# Laserschwert.net
KiCad netlist of a schematic drawn in EAGLE
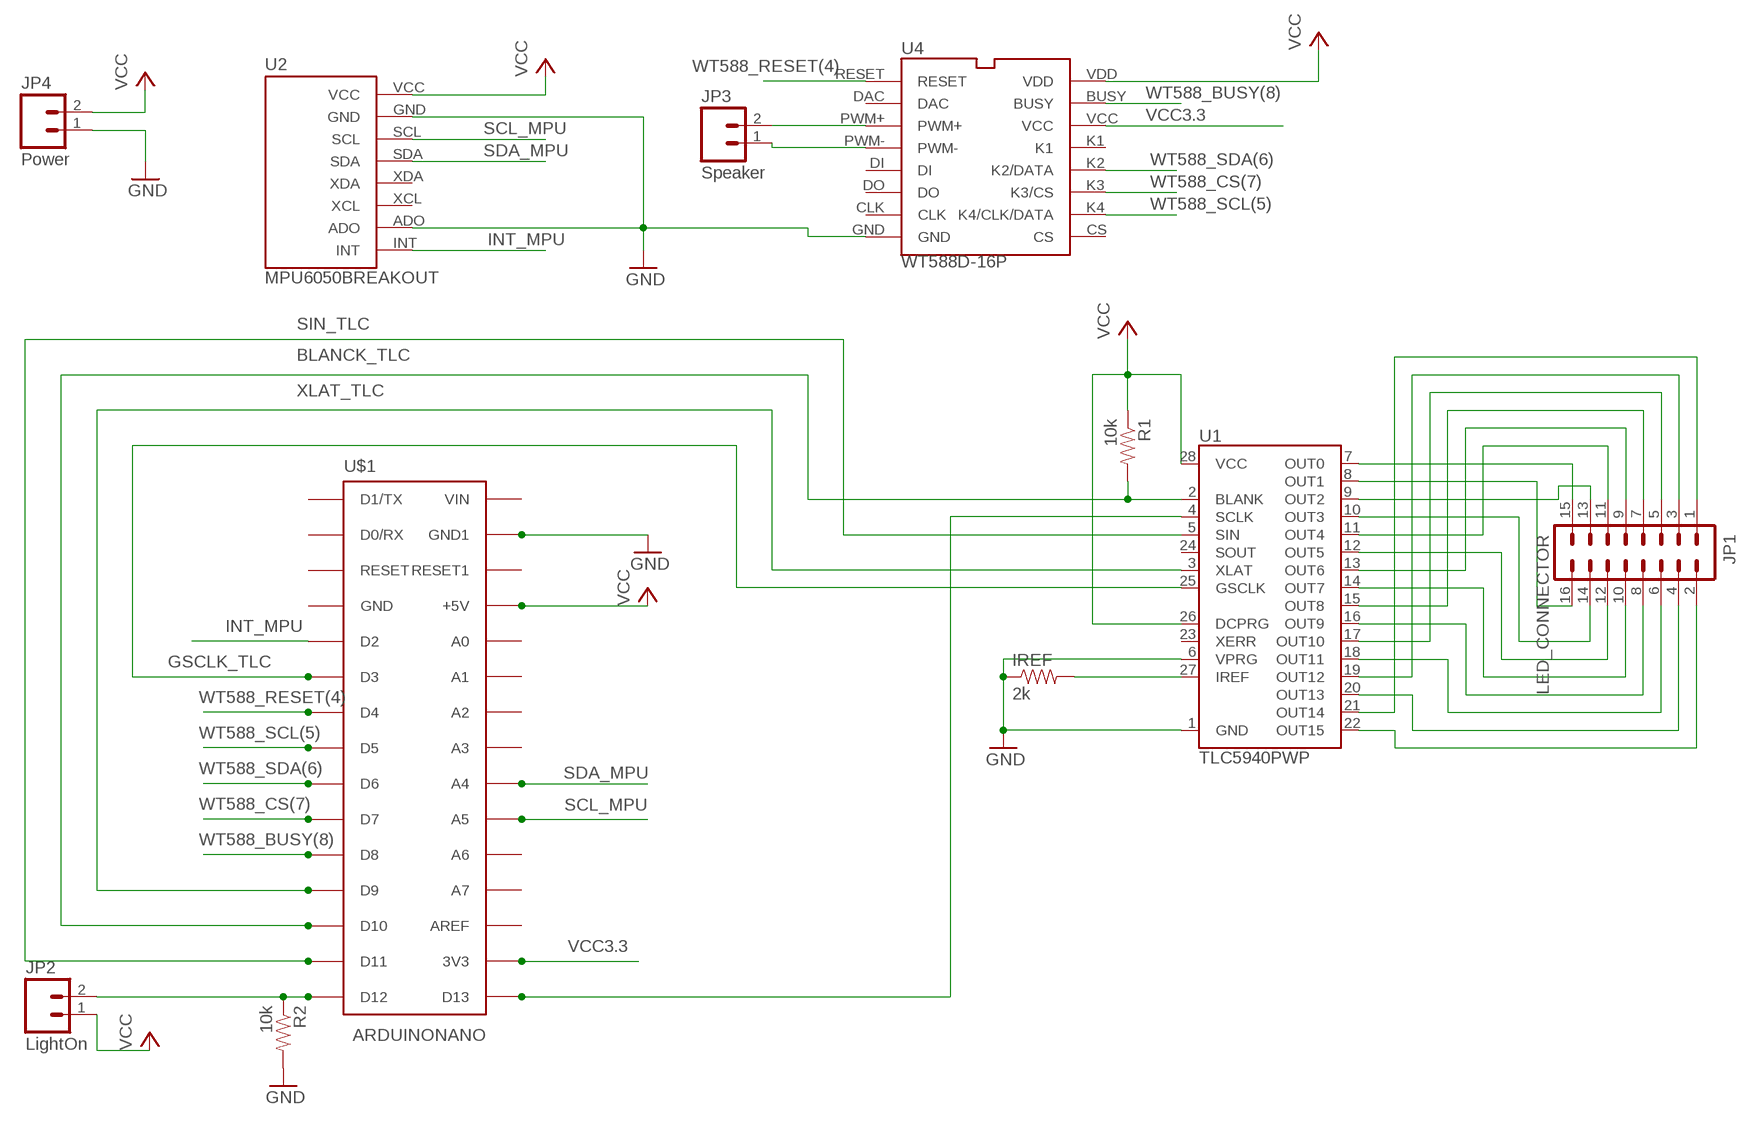
[diagram p0: schematic, sheet 1]

(export (version "E")
  (design (tool "Eeschema 10.0.6"))
  (components
    (comp (ref "IREF")
      (value "2k")
      (footprint "eagle-import:0805")
      (libsource (lib "eagle-import") (part "RESISTOR0805-RES"))
    )
    (comp (ref "JP1")
      (value "LED_CONNECTOR")
      (footprint "eagle-import:2X8")
      (libsource (lib "eagle-import") (part "M08X2"))
    )
    (comp (ref "JP2")
      (value "LightOn")
      (footprint "eagle-import:1X02")
      (libsource (lib "eagle-import") (part "M02PTH"))
    )
    (comp (ref "JP3")
      (value "Speaker")
      (footprint "eagle-import:1X02")
      (libsource (lib "eagle-import") (part "M02PTH"))
    )
    (comp (ref "JP4")
      (value "Power")
      (footprint "eagle-import:1X02")
      (libsource (lib "eagle-import") (part "M02PTH"))
    )
    (comp (ref "R1")
      (value "10k")
      (footprint "eagle-import:0805")
      (libsource (lib "eagle-import") (part "RESISTOR0805-RES"))
    )
    (comp (ref "R2")
      (value "10k")
      (footprint "eagle-import:0805")
      (libsource (lib "eagle-import") (part "RESISTOR0805-RES"))
    )
    (comp (ref "U$1")
      (value "ARDUINONANO")
      (footprint "eagle-import:PDIP-32")
      (libsource (lib "eagle-import") (part "ARDUINONANO"))
    )
    (comp (ref "U1")
      (value "TLC5940PWP")
      (footprint "eagle-import:TSSOP28-GROUNDPAD")
      (libsource (lib "eagle-import") (part "TLC5940PWP"))
    )
    (comp (ref "U2")
      (value "MPU6050BREAKOUT")
      (footprint "eagle-import:PDIP-8")
      (libsource (lib "eagle-import") (part "MPU6050BREAKOUT"))
    )
    (comp (ref "U4")
      (value "WT588D-16P")
      (footprint "eagle-import:PDIP-16")
      (libsource (lib "eagle-import") (part "WT588D-16P"))
    )
  )
  (nets
    (net (code "1") (name "/BLANCK_TLC") (class "Default")
      (node (ref "R1") (pin "2") (pinfunction "2_2") (pintype "passive"))
      (node (ref "U$1") (pin "D10") (pinfunction "D10_D10") (pintype "bidirectional"))
      (node (ref "U1") (pin "2") (pinfunction "BLANK_2") (pintype "bidirectional"))
    )
    (net (code "2") (name "/GSCLK_TLC") (class "Default")
      (node (ref "U$1") (pin "D3") (pinfunction "D3_D3") (pintype "bidirectional"))
      (node (ref "U1") (pin "25") (pinfunction "GSCLK_25") (pintype "bidirectional"))
    )
    (net (code "3") (name "/INT_MPU") (class "Default")
      (node (ref "U$1") (pin "D2") (pinfunction "D2_D2") (pintype "bidirectional"))
      (node (ref "U2") (pin "INT") (pinfunction "INT_INT") (pintype "bidirectional"))
    )
    (net (code "4") (name "/SCL_MPU") (class "Default")
      (node (ref "U$1") (pin "A5") (pinfunction "A5_A5") (pintype "bidirectional"))
      (node (ref "U2") (pin "SCL") (pinfunction "SCL_SCL") (pintype "bidirectional"))
    )
    (net (code "5") (name "/SDA_MPU") (class "Default")
      (node (ref "U$1") (pin "A4") (pinfunction "A4_A4") (pintype "bidirectional"))
      (node (ref "U2") (pin "SDA") (pinfunction "SDA_SDA") (pintype "bidirectional"))
    )
    (net (code "6") (name "/SIN_TLC") (class "Default")
      (node (ref "U$1") (pin "D11") (pinfunction "D11_D11") (pintype "bidirectional"))
      (node (ref "U1") (pin "5") (pinfunction "SIN_5") (pintype "bidirectional"))
    )
    (net (code "7") (name "/VCC3.3") (class "Default")
      (node (ref "U$1") (pin "3V3") (pinfunction "3V3_3V3") (pintype "bidirectional"))
      (node (ref "U4") (pin "VCC") (pinfunction "VCC_VCC") (pintype "power_in"))
    )
    (net (code "8") (name "/WT588_BUSY(8)") (class "Default")
      (node (ref "U$1") (pin "D8") (pinfunction "D8_D8") (pintype "bidirectional"))
      (node (ref "U4") (pin "BUSY") (pinfunction "BUSY_BUSY") (pintype "output"))
    )
    (net (code "9") (name "/WT588_CS(7)") (class "Default")
      (node (ref "U$1") (pin "D7") (pinfunction "D7_D7") (pintype "bidirectional"))
      (node (ref "U4") (pin "K3") (pinfunction "K3/CS_K3") (pintype "bidirectional"))
    )
    (net (code "10") (name "/WT588_RESET(4)") (class "Default")
      (node (ref "U$1") (pin "D4") (pinfunction "D4_D4") (pintype "bidirectional"))
      (node (ref "U4") (pin "RESET") (pinfunction "RESET_RESET") (pintype "bidirectional"))
    )
    (net (code "11") (name "/WT588_SCL(5)") (class "Default")
      (node (ref "U$1") (pin "D5") (pinfunction "D5_D5") (pintype "bidirectional"))
      (node (ref "U4") (pin "K4") (pinfunction "K4/CLK/DATA_K4") (pintype "bidirectional"))
    )
    (net (code "12") (name "/WT588_SDA(6)") (class "Default")
      (node (ref "U$1") (pin "D6") (pinfunction "D6_D6") (pintype "bidirectional"))
      (node (ref "U4") (pin "K2") (pinfunction "K2/DATA_K2") (pintype "bidirectional"))
    )
    (net (code "13") (name "/XLAT_TLC") (class "Default")
      (node (ref "U$1") (pin "D9") (pinfunction "D9_D9") (pintype "bidirectional"))
      (node (ref "U1") (pin "3") (pinfunction "XLAT_3") (pintype "bidirectional"))
    )
    (net (code "14") (name "GND") (class "Default")
      (node (ref "IREF") (pin "1") (pinfunction "1_1") (pintype "passive"))
      (node (ref "JP4") (pin "1") (pinfunction "1_1") (pintype "passive"))
      (node (ref "R2") (pin "2") (pinfunction "2_2") (pintype "passive"))
      (node (ref "U$1") (pin "GND1") (pinfunction "GND1_GND1") (pintype "bidirectional"))
      (node (ref "U1") (pin "1") (pinfunction "GND_1") (pintype "bidirectional"))
      (node (ref "U1") (pin "6") (pinfunction "VPRG_6") (pintype "bidirectional"))
      (node (ref "U2") (pin "ADO") (pinfunction "ADO_ADO") (pintype "bidirectional"))
      (node (ref "U2") (pin "GND") (pinfunction "GND_GND") (pintype "power_in"))
      (node (ref "U4") (pin "GND") (pinfunction "GND_GND") (pintype "power_in"))
    )
    (net (code "15") (name "Net-(JP2-Pad2)") (class "Default")
      (node (ref "JP2") (pin "2") (pinfunction "2_2") (pintype "passive"))
      (node (ref "R2") (pin "1") (pinfunction "1_1") (pintype "passive"))
      (node (ref "U$1") (pin "D12") (pinfunction "D12_D12") (pintype "bidirectional"))
    )
    (net (code "16") (name "Net-(JP3-Pad1)") (class "Default")
      (node (ref "JP3") (pin "1") (pinfunction "1_1") (pintype "passive"))
      (node (ref "U4") (pin "PWM-") (pinfunction "PWM-_PWM-") (pintype "bidirectional"))
    )
    (net (code "17") (name "Net-(JP3-Pad2)") (class "Default")
      (node (ref "JP3") (pin "2") (pinfunction "2_2") (pintype "passive"))
      (node (ref "U4") (pin "PWM+") (pinfunction "PWM+_PWM+") (pintype "bidirectional"))
    )
    (net (code "18") (name "Net-(U1-IREF)") (class "Default")
      (node (ref "IREF") (pin "2") (pinfunction "2_2") (pintype "passive"))
      (node (ref "U1") (pin "27") (pinfunction "IREF_27") (pintype "bidirectional"))
    )
    (net (code "19") (name "Net-(U1-OUT0)") (class "Default")
      (node (ref "JP1") (pin "15") (pinfunction "15_15") (pintype "passive"))
      (node (ref "U1") (pin "7") (pinfunction "OUT0_7") (pintype "bidirectional"))
    )
    (net (code "20") (name "Net-(U1-OUT1)") (class "Default")
      (node (ref "JP1") (pin "16") (pinfunction "16_16") (pintype "passive"))
      (node (ref "U1") (pin "8") (pinfunction "OUT1_8") (pintype "bidirectional"))
    )
    (net (code "21") (name "Net-(U1-OUT2)") (class "Default")
      (node (ref "JP1") (pin "13") (pinfunction "13_13") (pintype "passive"))
      (node (ref "U1") (pin "9") (pinfunction "OUT2_9") (pintype "bidirectional"))
    )
    (net (code "22") (name "Net-(U1-OUT3)") (class "Default")
      (node (ref "JP1") (pin "14") (pinfunction "14_14") (pintype "passive"))
      (node (ref "U1") (pin "10") (pinfunction "OUT3_10") (pintype "bidirectional"))
    )
    (net (code "23") (name "Net-(U1-OUT4)") (class "Default")
      (node (ref "JP1") (pin "11") (pinfunction "11_11") (pintype "passive"))
      (node (ref "U1") (pin "11") (pinfunction "OUT4_11") (pintype "bidirectional"))
    )
    (net (code "24") (name "Net-(U1-OUT5)") (class "Default")
      (node (ref "JP1") (pin "12") (pinfunction "12_12") (pintype "passive"))
      (node (ref "U1") (pin "12") (pinfunction "OUT5_12") (pintype "bidirectional"))
    )
    (net (code "25") (name "Net-(U1-OUT6)") (class "Default")
      (node (ref "JP1") (pin "9") (pinfunction "9_9") (pintype "passive"))
      (node (ref "U1") (pin "13") (pinfunction "OUT6_13") (pintype "bidirectional"))
    )
    (net (code "26") (name "Net-(U1-OUT7)") (class "Default")
      (node (ref "JP1") (pin "10") (pinfunction "10_10") (pintype "passive"))
      (node (ref "U1") (pin "14") (pinfunction "OUT7_14") (pintype "bidirectional"))
    )
    (net (code "27") (name "Net-(U1-OUT8)") (class "Default")
      (node (ref "JP1") (pin "7") (pinfunction "7_7") (pintype "passive"))
      (node (ref "U1") (pin "15") (pinfunction "OUT8_15") (pintype "bidirectional"))
    )
    (net (code "28") (name "Net-(U1-OUT9)") (class "Default")
      (node (ref "JP1") (pin "8") (pinfunction "8_8") (pintype "passive"))
      (node (ref "U1") (pin "16") (pinfunction "OUT9_16") (pintype "bidirectional"))
    )
    (net (code "29") (name "Net-(U1-OUT10)") (class "Default")
      (node (ref "JP1") (pin "5") (pinfunction "5_5") (pintype "passive"))
      (node (ref "U1") (pin "17") (pinfunction "OUT10_17") (pintype "bidirectional"))
    )
    (net (code "30") (name "Net-(U1-OUT11)") (class "Default")
      (node (ref "JP1") (pin "6") (pinfunction "6_6") (pintype "passive"))
      (node (ref "U1") (pin "18") (pinfunction "OUT11_18") (pintype "bidirectional"))
    )
    (net (code "31") (name "Net-(U1-OUT12)") (class "Default")
      (node (ref "JP1") (pin "3") (pinfunction "3_3") (pintype "passive"))
      (node (ref "U1") (pin "19") (pinfunction "OUT12_19") (pintype "bidirectional"))
    )
    (net (code "32") (name "Net-(U1-OUT13)") (class "Default")
      (node (ref "JP1") (pin "4") (pinfunction "4_4") (pintype "passive"))
      (node (ref "U1") (pin "20") (pinfunction "OUT13_20") (pintype "bidirectional"))
    )
    (net (code "33") (name "Net-(U1-OUT14)") (class "Default")
      (node (ref "JP1") (pin "1") (pinfunction "1_1") (pintype "passive"))
      (node (ref "U1") (pin "21") (pinfunction "OUT14_21") (pintype "bidirectional"))
    )
    (net (code "34") (name "Net-(U1-OUT15)") (class "Default")
      (node (ref "JP1") (pin "2") (pinfunction "2_2") (pintype "passive"))
      (node (ref "U1") (pin "22") (pinfunction "OUT15_22") (pintype "bidirectional"))
    )
    (net (code "35") (name "Net-(U1-SCLK)") (class "Default")
      (node (ref "U$1") (pin "D13") (pinfunction "D13_D13") (pintype "bidirectional"))
      (node (ref "U1") (pin "4") (pinfunction "SCLK_4") (pintype "bidirectional"))
    )
    (net (code "36") (name "VCC") (class "Default")
      (node (ref "JP2") (pin "1") (pinfunction "1_1") (pintype "passive"))
      (node (ref "JP4") (pin "2") (pinfunction "2_2") (pintype "passive"))
      (node (ref "R1") (pin "1") (pinfunction "1_1") (pintype "passive"))
      (node (ref "U$1") (pin "+5V") (pinfunction "+5V_+5V") (pintype "bidirectional"))
      (node (ref "U1") (pin "26") (pinfunction "DCPRG_26") (pintype "bidirectional"))
      (node (ref "U1") (pin "28") (pinfunction "VCC_28") (pintype "bidirectional"))
      (node (ref "U2") (pin "VCC") (pinfunction "VCC_VCC") (pintype "power_in"))
      (node (ref "U4") (pin "VDD") (pinfunction "VDD_VDD") (pintype "power_in"))
    )
    (net (code "37") (name "unconnected-(U$1-PadA0)") (class "Default")
      (node (ref "U$1") (pin "A0") (pinfunction "A0_A0") (pintype "bidirectional"))
    )
    (net (code "38") (name "unconnected-(U$1-PadA1)") (class "Default")
      (node (ref "U$1") (pin "A1") (pinfunction "A1_A1") (pintype "bidirectional"))
    )
    (net (code "39") (name "unconnected-(U$1-PadA2)") (class "Default")
      (node (ref "U$1") (pin "A2") (pinfunction "A2_A2") (pintype "bidirectional"))
    )
    (net (code "40") (name "unconnected-(U$1-PadA3)") (class "Default")
      (node (ref "U$1") (pin "A3") (pinfunction "A3_A3") (pintype "bidirectional"))
    )
    (net (code "41") (name "unconnected-(U$1-PadA6)") (class "Default")
      (node (ref "U$1") (pin "A6") (pinfunction "A6_A6") (pintype "bidirectional"))
    )
    (net (code "42") (name "unconnected-(U$1-PadA7)") (class "Default")
      (node (ref "U$1") (pin "A7") (pinfunction "A7_A7") (pintype "bidirectional"))
    )
    (net (code "43") (name "unconnected-(U$1-PadAREF)") (class "Default")
      (node (ref "U$1") (pin "AREF") (pinfunction "AREF_AREF") (pintype "bidirectional"))
    )
    (net (code "44") (name "unconnected-(U$1-PadD0{slash}RX)") (class "Default")
      (node (ref "U$1") (pin "D0/RX") (pinfunction "D0/RX_D0/RX") (pintype "bidirectional"))
    )
    (net (code "45") (name "unconnected-(U$1-PadD1{slash}TX)") (class "Default")
      (node (ref "U$1") (pin "D1/TX") (pinfunction "D1/TX_D1/TX") (pintype "bidirectional"))
    )
    (net (code "46") (name "unconnected-(U$1-PadGND)") (class "Default")
      (node (ref "U$1") (pin "GND") (pinfunction "GND_GND") (pintype "bidirectional"))
    )
    (net (code "47") (name "unconnected-(U$1-PadRESET)") (class "Default")
      (node (ref "U$1") (pin "RESET") (pinfunction "RESET_RESET") (pintype "bidirectional"))
    )
    (net (code "48") (name "unconnected-(U$1-PadRESET1)") (class "Default")
      (node (ref "U$1") (pin "RESET1") (pinfunction "RESET1_RESET1") (pintype "bidirectional"))
    )
    (net (code "49") (name "unconnected-(U$1-PadVIN)") (class "Default")
      (node (ref "U$1") (pin "VIN") (pinfunction "VIN_VIN") (pintype "bidirectional"))
    )
    (net (code "50") (name "unconnected-(U1-SOUT-Pad24)") (class "Default")
      (node (ref "U1") (pin "24") (pinfunction "SOUT_24") (pintype "bidirectional"))
    )
    (net (code "51") (name "unconnected-(U1-XERR-Pad23)") (class "Default")
      (node (ref "U1") (pin "23") (pinfunction "XERR_23") (pintype "bidirectional"))
    )
    (net (code "52") (name "unconnected-(U2-PadXCL)") (class "Default")
      (node (ref "U2") (pin "XCL") (pinfunction "XCL_XCL") (pintype "bidirectional"))
    )
    (net (code "53") (name "unconnected-(U2-PadXDA)") (class "Default")
      (node (ref "U2") (pin "XDA") (pinfunction "XDA_XDA") (pintype "bidirectional"))
    )
    (net (code "54") (name "unconnected-(U4-PadCLK)") (class "Default")
      (node (ref "U4") (pin "CLK") (pinfunction "CLK_CLK") (pintype "bidirectional"))
    )
    (net (code "55") (name "unconnected-(U4-PadCS)") (class "Default")
      (node (ref "U4") (pin "CS") (pinfunction "CS_CS") (pintype "bidirectional"))
    )
    (net (code "56") (name "unconnected-(U4-PadDAC)") (class "Default")
      (node (ref "U4") (pin "DAC") (pinfunction "DAC_DAC") (pintype "bidirectional"))
    )
    (net (code "57") (name "unconnected-(U4-PadDI)") (class "Default")
      (node (ref "U4") (pin "DI") (pinfunction "DI_DI") (pintype "bidirectional"))
    )
    (net (code "58") (name "unconnected-(U4-PadDO)") (class "Default")
      (node (ref "U4") (pin "DO") (pinfunction "DO_DO") (pintype "bidirectional"))
    )
    (net (code "59") (name "unconnected-(U4-PadK1)") (class "Default")
      (node (ref "U4") (pin "K1") (pinfunction "K1_K1") (pintype "bidirectional"))
    )
  )
)
